# dynalofet.net
KiCad netlist of a schematic drawn in EAGLE
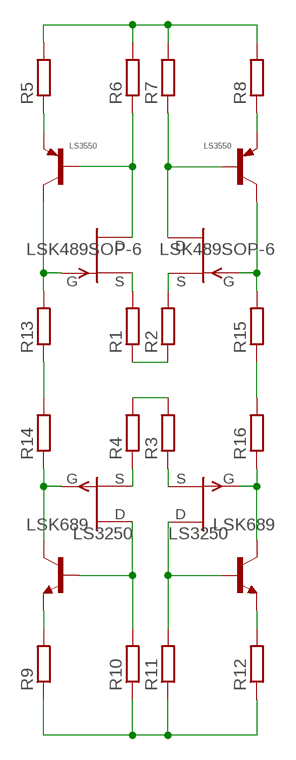
[diagram p0: schematic, sheet 1]

(export (version "E")
  (design (tool "Eeschema 10.0.6"))
  (components
    (comp (ref "Q1")
      (value "LS3250")
      (footprint "eagle-import:SOT-23-6")
      (libsource (lib "eagle-import") (part "LS3250"))
    )
    (comp (ref "Q2")
      (value "LS3550")
      (footprint "eagle-import:SOT-23-6")
      (libsource (lib "eagle-import") (part "LS3550"))
    )
    (comp (ref "Q3")
      (value "LSK489SOP-6")
      (footprint "eagle-import:SOT-23-6")
      (libsource (lib "eagle-import") (part "LSK489SOP-6"))
    )
    (comp (ref "Q4")
      (value "LSK689")
      (footprint "eagle-import:SOT-23-6")
      (libsource (lib "eagle-import") (part "LSK689"))
    )
    (comp (ref "R1")
      (value "R-EU_MELF0204W")
      (footprint "eagle-import:MINI_MELF-0204W")
      (libsource (lib "eagle-import") (part "R-EU_MELF0204W"))
    )
    (comp (ref "R2")
      (value "R-EU_MELF0204W")
      (footprint "eagle-import:MINI_MELF-0204W")
      (libsource (lib "eagle-import") (part "R-EU_MELF0204W"))
    )
    (comp (ref "R3")
      (value "R-EU_MELF0204W")
      (footprint "eagle-import:MINI_MELF-0204W")
      (libsource (lib "eagle-import") (part "R-EU_MELF0204W"))
    )
    (comp (ref "R4")
      (value "R-EU_MELF0204W")
      (footprint "eagle-import:MINI_MELF-0204W")
      (libsource (lib "eagle-import") (part "R-EU_MELF0204W"))
    )
    (comp (ref "R5")
      (value "R-EU_MELF0204W")
      (footprint "eagle-import:MINI_MELF-0204W")
      (libsource (lib "eagle-import") (part "R-EU_MELF0204W"))
    )
    (comp (ref "R6")
      (value "R-EU_MELF0204W")
      (footprint "eagle-import:MINI_MELF-0204W")
      (libsource (lib "eagle-import") (part "R-EU_MELF0204W"))
    )
    (comp (ref "R7")
      (value "R-EU_MELF0204W")
      (footprint "eagle-import:MINI_MELF-0204W")
      (libsource (lib "eagle-import") (part "R-EU_MELF0204W"))
    )
    (comp (ref "R8")
      (value "R-EU_MELF0204W")
      (footprint "eagle-import:MINI_MELF-0204W")
      (libsource (lib "eagle-import") (part "R-EU_MELF0204W"))
    )
    (comp (ref "R9")
      (value "R-EU_MELF0204W")
      (footprint "eagle-import:MINI_MELF-0204W")
      (libsource (lib "eagle-import") (part "R-EU_MELF0204W"))
    )
    (comp (ref "R10")
      (value "R-EU_MELF0204W")
      (footprint "eagle-import:MINI_MELF-0204W")
      (libsource (lib "eagle-import") (part "R-EU_MELF0204W"))
    )
    (comp (ref "R11")
      (value "R-EU_MELF0204W")
      (footprint "eagle-import:MINI_MELF-0204W")
      (libsource (lib "eagle-import") (part "R-EU_MELF0204W"))
    )
    (comp (ref "R12")
      (value "R-EU_MELF0204W")
      (footprint "eagle-import:MINI_MELF-0204W")
      (libsource (lib "eagle-import") (part "R-EU_MELF0204W"))
    )
    (comp (ref "R13")
      (value "R-EU_MELF0204W")
      (footprint "eagle-import:MINI_MELF-0204W")
      (libsource (lib "eagle-import") (part "R-EU_MELF0204W"))
    )
    (comp (ref "R14")
      (value "R-EU_MELF0204W")
      (footprint "eagle-import:MINI_MELF-0204W")
      (libsource (lib "eagle-import") (part "R-EU_MELF0204W"))
    )
    (comp (ref "R15")
      (value "R-EU_MELF0204W")
      (footprint "eagle-import:MINI_MELF-0204W")
      (libsource (lib "eagle-import") (part "R-EU_MELF0204W"))
    )
    (comp (ref "R16")
      (value "R-EU_MELF0204W")
      (footprint "eagle-import:MINI_MELF-0204W")
      (libsource (lib "eagle-import") (part "R-EU_MELF0204W"))
    )
  )
  (nets
    (net (code "1") (name "Net-(Q1A-B)") (class "Default")
      (node (ref "Q1") (pin "1") (pinfunction "B_1") (pintype "passive"))
      (node (ref "Q4") (pin "2") (pinfunction "D_2") (pintype "passive"))
      (node (ref "R11") (pin "2") (pinfunction "2_2") (pintype "passive"))
    )
    (net (code "2") (name "Net-(Q1A-C)") (class "Default")
      (node (ref "Q1") (pin "6") (pinfunction "C_6") (pintype "passive"))
      (node (ref "Q4") (pin "1") (pinfunction "G_1") (pintype "passive"))
      (node (ref "R16") (pin "1") (pinfunction "1_1") (pintype "passive"))
    )
    (net (code "3") (name "Net-(Q1A-E)") (class "Default")
      (node (ref "Q1") (pin "5") (pinfunction "E_5") (pintype "passive"))
      (node (ref "R12") (pin "2") (pinfunction "2_2") (pintype "passive"))
    )
    (net (code "4") (name "Net-(Q1B-B)") (class "Default")
      (node (ref "Q1") (pin "3") (pinfunction "B_3") (pintype "passive"))
      (node (ref "Q4") (pin "5") (pinfunction "D_5") (pintype "passive"))
      (node (ref "R10") (pin "2") (pinfunction "2_2") (pintype "passive"))
    )
    (net (code "5") (name "Net-(Q1B-C)") (class "Default")
      (node (ref "Q1") (pin "4") (pinfunction "C_4") (pintype "passive"))
      (node (ref "Q4") (pin "4") (pinfunction "G_4") (pintype "passive"))
      (node (ref "R14") (pin "1") (pinfunction "1_1") (pintype "passive"))
    )
    (net (code "6") (name "Net-(Q1B-E)") (class "Default")
      (node (ref "Q1") (pin "2") (pinfunction "E_2") (pintype "passive"))
      (node (ref "R9") (pin "2") (pinfunction "2_2") (pintype "passive"))
    )
    (net (code "7") (name "Net-(Q2A-B)") (class "Default")
      (node (ref "Q2") (pin "1") (pinfunction "B_1") (pintype "passive"))
      (node (ref "Q3") (pin "2") (pinfunction "D_2") (pintype "passive"))
      (node (ref "R7") (pin "1") (pinfunction "1_1") (pintype "passive"))
    )
    (net (code "8") (name "Net-(Q2A-C)") (class "Default")
      (node (ref "Q2") (pin "6") (pinfunction "C_6") (pintype "passive"))
      (node (ref "Q3") (pin "1") (pinfunction "G_1") (pintype "passive"))
      (node (ref "R15") (pin "2") (pinfunction "2_2") (pintype "passive"))
    )
    (net (code "9") (name "Net-(Q2A-E)") (class "Default")
      (node (ref "Q2") (pin "5") (pinfunction "E_5") (pintype "passive"))
      (node (ref "R8") (pin "1") (pinfunction "1_1") (pintype "passive"))
    )
    (net (code "10") (name "Net-(Q2B-B)") (class "Default")
      (node (ref "Q2") (pin "3") (pinfunction "B_3") (pintype "passive"))
      (node (ref "Q3") (pin "5") (pinfunction "D_5") (pintype "passive"))
      (node (ref "R6") (pin "1") (pinfunction "1_1") (pintype "passive"))
    )
    (net (code "11") (name "Net-(Q2B-C)") (class "Default")
      (node (ref "Q2") (pin "4") (pinfunction "C_4") (pintype "passive"))
      (node (ref "Q3") (pin "4") (pinfunction "G_4") (pintype "passive"))
      (node (ref "R13") (pin "2") (pinfunction "2_2") (pintype "passive"))
    )
    (net (code "12") (name "Net-(Q2B-E)") (class "Default")
      (node (ref "Q2") (pin "2") (pinfunction "E_2") (pintype "passive"))
      (node (ref "R5") (pin "1") (pinfunction "1_1") (pintype "passive"))
    )
    (net (code "13") (name "Net-(Q3A-S)") (class "Default")
      (node (ref "Q3") (pin "3") (pinfunction "S_3") (pintype "passive"))
      (node (ref "R2") (pin "2") (pinfunction "2_2") (pintype "passive"))
    )
    (net (code "14") (name "Net-(Q3B-S)") (class "Default")
      (node (ref "Q3") (pin "6") (pinfunction "S_6") (pintype "passive"))
      (node (ref "R1") (pin "2") (pinfunction "2_2") (pintype "passive"))
    )
    (net (code "15") (name "Net-(Q4A-S)") (class "Default")
      (node (ref "Q4") (pin "3") (pinfunction "S_3") (pintype "passive"))
      (node (ref "R3") (pin "1") (pinfunction "1_1") (pintype "passive"))
    )
    (net (code "16") (name "Net-(Q4B-S)") (class "Default")
      (node (ref "Q4") (pin "6") (pinfunction "S_6") (pintype "passive"))
      (node (ref "R4") (pin "1") (pinfunction "1_1") (pintype "passive"))
    )
    (net (code "17") (name "Net-(R1-Pad1)") (class "Default")
      (node (ref "R1") (pin "1") (pinfunction "1_1") (pintype "passive"))
      (node (ref "R2") (pin "1") (pinfunction "1_1") (pintype "passive"))
    )
    (net (code "18") (name "Net-(R3-Pad2)") (class "Default")
      (node (ref "R3") (pin "2") (pinfunction "2_2") (pintype "passive"))
      (node (ref "R4") (pin "2") (pinfunction "2_2") (pintype "passive"))
    )
    (net (code "19") (name "Net-(R5-Pad2)") (class "Default")
      (node (ref "R5") (pin "2") (pinfunction "2_2") (pintype "passive"))
      (node (ref "R6") (pin "2") (pinfunction "2_2") (pintype "passive"))
      (node (ref "R7") (pin "2") (pinfunction "2_2") (pintype "passive"))
      (node (ref "R8") (pin "2") (pinfunction "2_2") (pintype "passive"))
    )
    (net (code "20") (name "Net-(R10-Pad1)") (class "Default")
      (node (ref "R10") (pin "1") (pinfunction "1_1") (pintype "passive"))
      (node (ref "R11") (pin "1") (pinfunction "1_1") (pintype "passive"))
      (node (ref "R12") (pin "1") (pinfunction "1_1") (pintype "passive"))
      (node (ref "R9") (pin "1") (pinfunction "1_1") (pintype "passive"))
    )
    (net (code "21") (name "Net-(R13-Pad1)") (class "Default")
      (node (ref "R13") (pin "1") (pinfunction "1_1") (pintype "passive"))
      (node (ref "R14") (pin "2") (pinfunction "2_2") (pintype "passive"))
    )
    (net (code "22") (name "Net-(R15-Pad1)") (class "Default")
      (node (ref "R15") (pin "1") (pinfunction "1_1") (pintype "passive"))
      (node (ref "R16") (pin "2") (pinfunction "2_2") (pintype "passive"))
    )
  )
)
